# MegaTinyTimeWatch.net
KiCad netlist of a schematic drawn in EAGLE
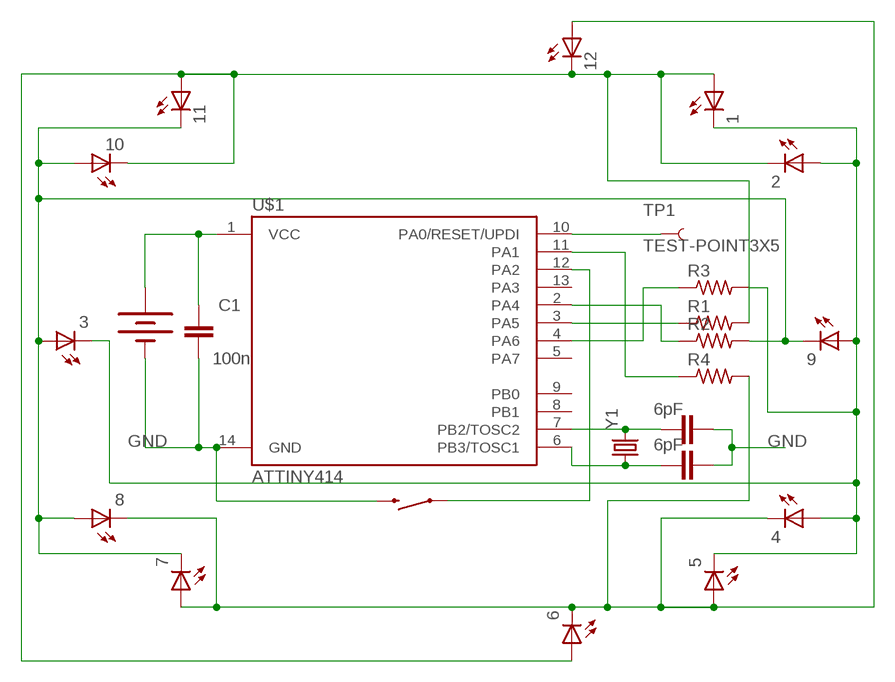
[diagram p0: schematic, sheet 1]

(export (version "E")
  (design (tool "Eeschema 10.0.6"))
  (components
    (comp (ref "1")
      (value "LEDCHIPLED_0805")
      (footprint "eagle-import:CHIPLED_0805")
      (libsource (lib "eagle-import") (part "LEDCHIPLED_0805"))
    )
    (comp (ref "2")
      (value "LEDCHIPLED_0805")
      (footprint "eagle-import:CHIPLED_0805")
      (libsource (lib "eagle-import") (part "LEDCHIPLED_0805"))
    )
    (comp (ref "3")
      (value "LEDCHIPLED_0805")
      (footprint "eagle-import:CHIPLED_0805")
      (libsource (lib "eagle-import") (part "LEDCHIPLED_0805"))
    )
    (comp (ref "4")
      (value "LEDCHIPLED_0805")
      (footprint "eagle-import:CHIPLED_0805")
      (libsource (lib "eagle-import") (part "LEDCHIPLED_0805"))
    )
    (comp (ref "5")
      (value "LEDCHIPLED_0805")
      (footprint "eagle-import:CHIPLED_0805")
      (libsource (lib "eagle-import") (part "LEDCHIPLED_0805"))
    )
    (comp (ref "6")
      (value "LEDCHIPLED_0805")
      (footprint "eagle-import:CHIPLED_0805")
      (libsource (lib "eagle-import") (part "LEDCHIPLED_0805"))
    )
    (comp (ref "7")
      (value "LEDCHIPLED_0805")
      (footprint "eagle-import:CHIPLED_0805")
      (libsource (lib "eagle-import") (part "LEDCHIPLED_0805"))
    )
    (comp (ref "8")
      (value "LEDCHIPLED_0805")
      (footprint "eagle-import:CHIPLED_0805")
      (libsource (lib "eagle-import") (part "LEDCHIPLED_0805"))
    )
    (comp (ref "9")
      (value "LEDCHIPLED_0805")
      (footprint "eagle-import:CHIPLED_0805")
      (libsource (lib "eagle-import") (part "LEDCHIPLED_0805"))
    )
    (comp (ref "10")
      (value "LEDCHIPLED_0805")
      (footprint "eagle-import:CHIPLED_0805")
      (libsource (lib "eagle-import") (part "LEDCHIPLED_0805"))
    )
    (comp (ref "11")
      (value "LEDCHIPLED_0805")
      (footprint "eagle-import:CHIPLED_0805")
      (libsource (lib "eagle-import") (part "LEDCHIPLED_0805"))
    )
    (comp (ref "12")
      (value "LEDCHIPLED_0805")
      (footprint "eagle-import:CHIPLED_0805")
      (libsource (lib "eagle-import") (part "LEDCHIPLED_0805"))
    )
    (comp (ref "BAT1")
      (value "20mm coincell")
      (footprint "eagle-import:BATTCON_20MM_4LEGS")
      (libsource (lib "eagle-import") (part "BATTERY20MM_4LEGS"))
    )
    (comp (ref "C1")
      (value "100n")
      (footprint "eagle-import:0603-CAP")
      (libsource (lib "eagle-import") (part "CAP0603-CAP"))
    )
    (comp (ref "C2")
      (value "6pF")
      (footprint "eagle-import:0603-CAP")
      (libsource (lib "eagle-import") (part "CAP0603-CAP"))
    )
    (comp (ref "C12")
      (value "6pF")
      (footprint "eagle-import:0603-CAP")
      (libsource (lib "eagle-import") (part "CAP0603-CAP"))
    )
    (comp (ref "R1")
      (value "R-US_M0805")
      (footprint "eagle-import:M0805")
      (libsource (lib "eagle-import") (part "R-US_M0805"))
    )
    (comp (ref "R2")
      (value "R-US_M0805")
      (footprint "eagle-import:M0805")
      (libsource (lib "eagle-import") (part "R-US_M0805"))
    )
    (comp (ref "R3")
      (value "R-US_M0805")
      (footprint "eagle-import:M0805")
      (libsource (lib "eagle-import") (part "R-US_M0805"))
    )
    (comp (ref "R4")
      (value "R-US_M0805")
      (footprint "eagle-import:M0805")
      (libsource (lib "eagle-import") (part "R-US_M0805"))
    )
    (comp (ref "S2")
      (value "SWITCH-MOMENTARY-2SMD")
      (footprint "eagle-import:TACTILE-SWITCH-SMD")
      (libsource (lib "eagle-import") (part "SWITCH-MOMENTARY-2SMD"))
    )
    (comp (ref "TP1")
      (value "TEST-POINT3X5")
      (footprint "eagle-import:PAD.03X.05")
      (libsource (lib "eagle-import") (part "TEST-POINT3X5"))
    )
    (comp (ref "U$1")
      (value "ATTINY414")
      (footprint "eagle-import:SO14")
      (libsource (lib "eagle-import") (part "ATTINY414"))
    )
    (comp (ref "Y1")
      (value "CRYSTAL32-SMD-MELF")
      (footprint "eagle-import:CRYSTAL-32KHZ-SMD-MELF")
      (libsource (lib "eagle-import") (part "CRYSTAL32-SMD-MELF"))
    )
  )
  (nets
    (net (code "1") (name "/GND") (class "Default")
      (node (ref "BAT1") (pin "NEGATIVE") (pinfunction "-_NEGATIVE") (pintype "power_in"))
      (node (ref "C1") (pin "2") (pinfunction "2_2") (pintype "passive"))
      (node (ref "C12") (pin "1") (pinfunction "1_1") (pintype "passive"))
      (node (ref "C2") (pin "1") (pinfunction "1_1") (pintype "passive"))
      (node (ref "S2") (pin "3") (pinfunction "2_3") (pintype "passive"))
      (node (ref "U$1") (pin "14") (pinfunction "GND_14") (pintype "bidirectional"))
    )
    (net (code "2") (name "Net-(1-PadA)") (class "Default")
      (node (ref "1") (pin "A") (pinfunction "A_A") (pintype "passive"))
      (node (ref "10") (pin "C") (pinfunction "C_C") (pintype "passive"))
      (node (ref "11") (pin "A") (pinfunction "A_A") (pintype "passive"))
      (node (ref "12") (pin "C") (pinfunction "C_C") (pintype "passive"))
      (node (ref "2") (pin "C") (pinfunction "C_C") (pintype "passive"))
      (node (ref "6") (pin "A") (pinfunction "A_A") (pintype "passive"))
      (node (ref "R1") (pin "2") (pinfunction "2_2") (pintype "passive"))
    )
    (net (code "3") (name "Net-(1-PadC)") (class "Default")
      (node (ref "1") (pin "C") (pinfunction "C_C") (pintype "passive"))
      (node (ref "2") (pin "A") (pinfunction "A_A") (pintype "passive"))
      (node (ref "3") (pin "C") (pinfunction "C_C") (pintype "passive"))
      (node (ref "4") (pin "A") (pinfunction "A_A") (pintype "passive"))
      (node (ref "5") (pin "C") (pinfunction "C_C") (pintype "passive"))
      (node (ref "9") (pin "A") (pinfunction "A_A") (pintype "passive"))
      (node (ref "R3") (pin "2") (pinfunction "2_2") (pintype "passive"))
    )
    (net (code "4") (name "Net-(10-PadA)") (class "Default")
      (node (ref "10") (pin "A") (pinfunction "A_A") (pintype "passive"))
      (node (ref "11") (pin "C") (pinfunction "C_C") (pintype "passive"))
      (node (ref "3") (pin "A") (pinfunction "A_A") (pintype "passive"))
      (node (ref "7") (pin "C") (pinfunction "C_C") (pintype "passive"))
      (node (ref "8") (pin "A") (pinfunction "A_A") (pintype "passive"))
      (node (ref "9") (pin "C") (pinfunction "C_C") (pintype "passive"))
      (node (ref "R2") (pin "2") (pinfunction "2_2") (pintype "passive"))
    )
    (net (code "5") (name "Net-(12-PadA)") (class "Default")
      (node (ref "12") (pin "A") (pinfunction "A_A") (pintype "passive"))
      (node (ref "4") (pin "C") (pinfunction "C_C") (pintype "passive"))
      (node (ref "5") (pin "A") (pinfunction "A_A") (pintype "passive"))
      (node (ref "6") (pin "C") (pinfunction "C_C") (pintype "passive"))
      (node (ref "7") (pin "A") (pinfunction "A_A") (pintype "passive"))
      (node (ref "8") (pin "C") (pinfunction "C_C") (pintype "passive"))
      (node (ref "R4") (pin "2") (pinfunction "2_2") (pintype "passive"))
    )
    (net (code "6") (name "Net-(TP1-1)") (class "Default")
      (node (ref "TP1") (pin "P$1") (pinfunction "1_P$1") (pintype "bidirectional"))
      (node (ref "U$1") (pin "10") (pinfunction "PA0/RESET/UPDI_10") (pintype "bidirectional"))
    )
    (net (code "7") (name "Net-(U$1-PA1)") (class "Default")
      (node (ref "R4") (pin "1") (pinfunction "1_1") (pintype "passive"))
      (node (ref "U$1") (pin "11") (pinfunction "PA1_11") (pintype "bidirectional"))
    )
    (net (code "8") (name "Net-(U$1-PA2)") (class "Default")
      (node (ref "S2") (pin "1") (pinfunction "1_1") (pintype "passive"))
      (node (ref "U$1") (pin "12") (pinfunction "PA2_12") (pintype "bidirectional"))
    )
    (net (code "9") (name "Net-(U$1-PA4)") (class "Default")
      (node (ref "R2") (pin "1") (pinfunction "1_1") (pintype "passive"))
      (node (ref "U$1") (pin "2") (pinfunction "PA4_2") (pintype "bidirectional"))
    )
    (net (code "10") (name "Net-(U$1-PA5)") (class "Default")
      (node (ref "R1") (pin "1") (pinfunction "1_1") (pintype "passive"))
      (node (ref "U$1") (pin "3") (pinfunction "PA5_3") (pintype "bidirectional"))
    )
    (net (code "11") (name "Net-(U$1-PA6)") (class "Default")
      (node (ref "R3") (pin "1") (pinfunction "1_1") (pintype "passive"))
      (node (ref "U$1") (pin "4") (pinfunction "PA6_4") (pintype "bidirectional"))
    )
    (net (code "12") (name "Net-(U$1-PB2{slash}TOSC2)") (class "Default")
      (node (ref "C12") (pin "2") (pinfunction "2_2") (pintype "passive"))
      (node (ref "U$1") (pin "7") (pinfunction "PB2/TOSC2_7") (pintype "bidirectional"))
      (node (ref "Y1") (pin "X2") (pinfunction "2_X2") (pintype "passive"))
    )
    (net (code "13") (name "Net-(U$1-PB3{slash}TOSC1)") (class "Default")
      (node (ref "C2") (pin "2") (pinfunction "2_2") (pintype "passive"))
      (node (ref "U$1") (pin "6") (pinfunction "PB3/TOSC1_6") (pintype "bidirectional"))
      (node (ref "Y1") (pin "X1") (pinfunction "1_X1") (pintype "passive"))
    )
    (net (code "14") (name "Net-(U$1-VCC)") (class "Default")
      (node (ref "BAT1") (pin "POSITIVE@1") (pinfunction "+_POSITIVE@1") (pintype "power_in"))
      (node (ref "BAT1") (pin "POSITIVE@2") (pinfunction "+_POSITIVE@2") (pintype "power_in"))
      (node (ref "BAT1") (pin "POSITIVE@3") (pinfunction "+_POSITIVE@3") (pintype "power_in"))
      (node (ref "BAT1") (pin "POSITIVE@4") (pinfunction "+_POSITIVE@4") (pintype "power_in"))
      (node (ref "C1") (pin "1") (pinfunction "1_1") (pintype "passive"))
      (node (ref "U$1") (pin "1") (pinfunction "VCC_1") (pintype "bidirectional"))
    )
    (net (code "15") (name "unconnected-(U$1-PA3-Pad13)") (class "Default")
      (node (ref "U$1") (pin "13") (pinfunction "PA3_13") (pintype "bidirectional"))
    )
    (net (code "16") (name "unconnected-(U$1-PA7-Pad5)") (class "Default")
      (node (ref "U$1") (pin "5") (pinfunction "PA7_5") (pintype "bidirectional"))
    )
    (net (code "17") (name "unconnected-(U$1-PB0-Pad9)") (class "Default")
      (node (ref "U$1") (pin "9") (pinfunction "PB0_9") (pintype "bidirectional"))
    )
    (net (code "18") (name "unconnected-(U$1-PB1-Pad8)") (class "Default")
      (node (ref "U$1") (pin "8") (pinfunction "PB1_8") (pintype "bidirectional"))
    )
  )
)
